# Power_Conditioning.net
KiCad netlist of a schematic drawn in Altium Designer
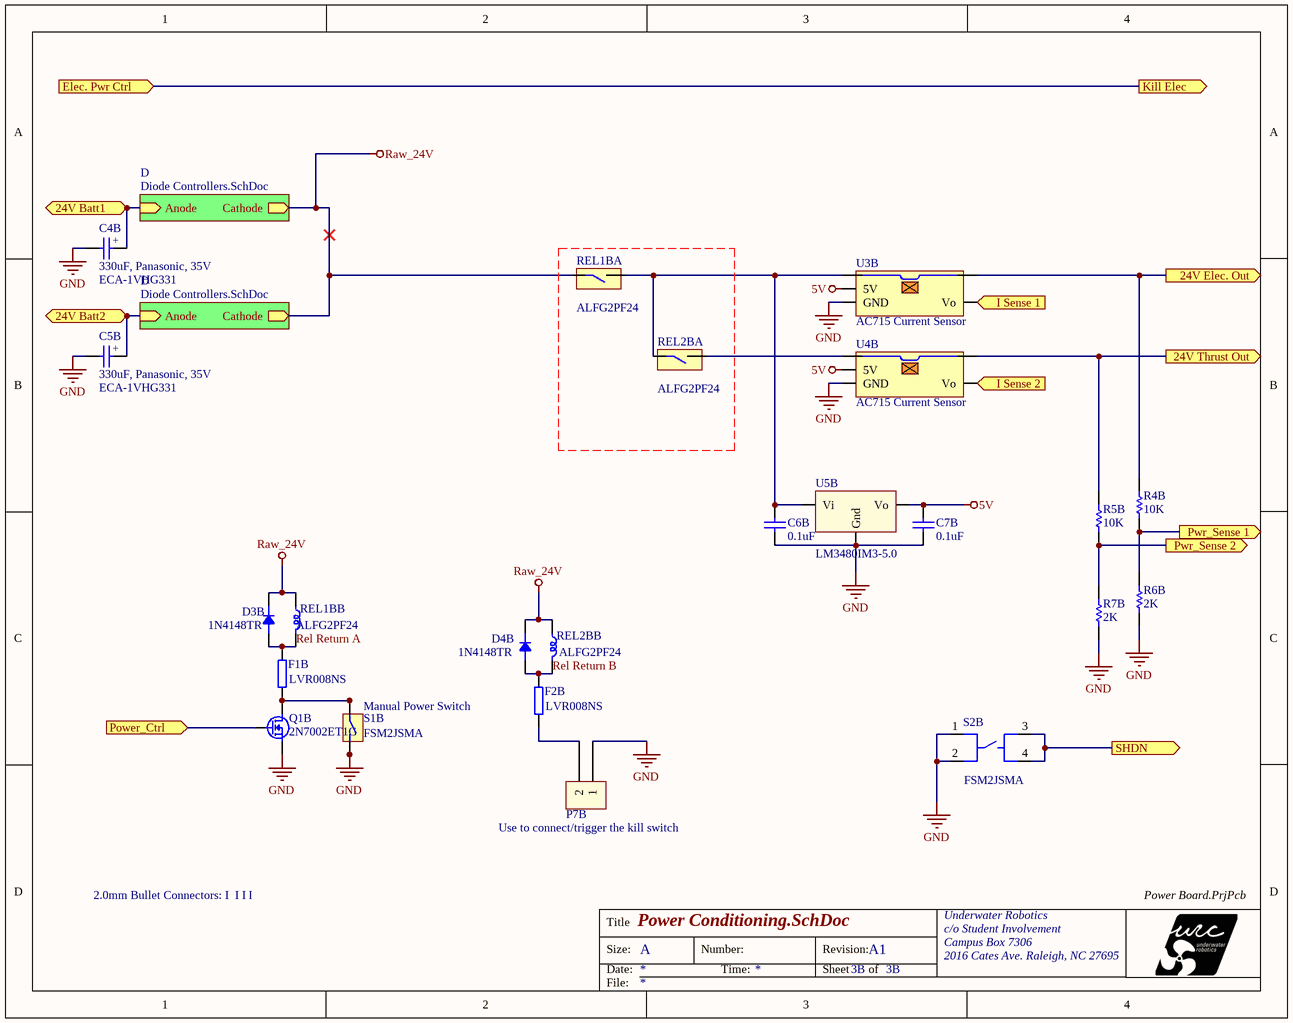
[diagram p0: Power Conditioning.SchDoc]

(export (version "E")
  (design (tool "Eeschema 10.0.6"))
  (components
    (comp (ref "C4B")
      (value "330uF, Panasonic, 35V")
      (footprint "10mm Radial Cap, Generic")
      (fields (field (name "MANUFACTURER PART NUMBER") "ECA-1VHG331"))
      (libsource (lib "Capacitors SchLib") (part "330uF, Panasonic, 35V"))
    )
    (comp (ref "C5B")
      (value "330uF, Panasonic, 35V")
      (footprint "10mm Radial Cap, Generic")
      (fields (field (name "MANUFACTURER PART NUMBER") "ECA-1VHG331"))
      (libsource (lib "Capacitors SchLib") (part "330uF, Panasonic, 35V"))
    )
    (comp (ref "C6B")
      (value "0.1uF")
      (footprint "C0805")
      (description "Ceramic MLCC, AVX, X5R Dielectric")
      (fields
        (field (name "MANUFACTURER PART NUMBER") "08055C104JAT2A")
        (field (name "Comment") "0.1uF, C0805, AVX")
      )
      (libsource (lib "Capacitors SchLib") (part "0.1uF, C0805, AVX"))
    )
    (comp (ref "C7B")
      (value "0.1uF")
      (footprint "C0805")
      (description "Ceramic MLCC, AVX, X5R Dielectric")
      (fields
        (field (name "MANUFACTURER PART NUMBER") "08055C104JAT2A")
        (field (name "Comment") "0.1uF, C0805, AVX")
      )
      (libsource (lib "Capacitors SchLib") (part "0.1uF, C0805, AVX"))
    )
    (comp (ref "D3B")
      (value "Diode")
      (footprint "DO-35-0.3")
      (description "General Purpose Diode")
      (fields (field (name "MANUFACTURER PART NUMBER") "1N4148TR"))
      (libsource (lib "URC") (part "Diode"))
    )
    (comp (ref "D4B")
      (value "Diode")
      (footprint "DO-35-0.3")
      (description "General Purpose Diode")
      (fields (field (name "MANUFACTURER PART NUMBER") "1N4148TR"))
      (libsource (lib "URC") (part "Diode"))
    )
    (comp (ref "F1B")
      (value "PTC Fuse, LVR008NS")
      (footprint "LVR008NS - Resettable Fuse")
      (description "Generic Fuse")
      (fields (field (name "MANUFACTURER PART NUMBER") "LVR008NS"))
      (libsource (lib "URC") (part "PTC Fuse, LVR008NS"))
    )
    (comp (ref "F2B")
      (value "PTC Fuse, LVR008NS")
      (footprint "LVR008NS - Resettable Fuse")
      (description "Generic Fuse")
      (fields (field (name "MANUFACTURER PART NUMBER") "LVR008NS"))
      (libsource (lib "URC") (part "PTC Fuse, LVR008NS"))
    )
    (comp (ref "i1B")
      (value "2.0mm Bullet Connector (Placeholder)")
      (description "Typical 2.0mm bullet connector used in RC Electronics")
      (libsource (lib "") (part "2.0mm Bullet Connector (Placeholder)_1"))
    )
    (comp (ref "i2B")
      (value "2.0mm Bullet Connector (Placeholder)")
      (description "Typical 2.0mm bullet connector used in RC Electronics")
      (libsource (lib "URC") (part "2.0mm Bullet Connector (Placeholder)"))
    )
    (comp (ref "i3B")
      (value "2.0mm Bullet Connector (Placeholder)")
      (description "Typical 2.0mm bullet connector used in RC Electronics")
      (libsource (lib "URC") (part "2.0mm Bullet Connector (Placeholder)"))
    )
    (comp (ref "i4B")
      (value "2.0mm Bullet Connector (Placeholder)")
      (description "Typical 2.0mm bullet connector used in RC Electronics")
      (libsource (lib "URC") (part "2.0mm Bullet Connector (Placeholder)"))
    )
    (comp (ref "P7B")
      (value "Header")
      (footprint "1x2 Header")
      (description "1x2 Header")
      (libsource (lib "URC_Lib") (part "1x2 Header"))
    )
    (comp (ref "Q1B")
      (value "N-MOSFET")
      (footprint "2N7002-SOT23")
      (description "N-Channel MOSFET")
      (fields (field (name "MANUFACTURER PART NUMBER") "2N7002ET1G"))
      (libsource (lib "URC") (part "N-MOSFET"))
    )
    (comp (ref "R4B")
      (value "10K")
      (footprint "R0603")
      (description "Resistor")
      (fields (field (name "TOLERANCE") "1%") (field (name "MANUFACTURER PART NUMBER") "RC0603FR-1010KL"))
      (libsource (lib "Resistors SchLib") (part "10k, 1%, 100mW, Yageo, R0603"))
    )
    (comp (ref "R5B")
      (value "10K")
      (footprint "R0603")
      (description "Resistor")
      (fields (field (name "TOLERANCE") "1%") (field (name "MANUFACTURER PART NUMBER") "RC0603FR-1010KL"))
      (libsource (lib "Resistors SchLib") (part "10k, 1%, 100mW, Yageo, R0603"))
    )
    (comp (ref "R6B")
      (value "2K")
      (footprint "R0603")
      (description "Resistor")
      (fields (field (name "TOLERANCE") "1%") (field (name "MANUFACTURER PART NUMBER") "RC0603FR-072KL"))
      (libsource (lib "Resistors SchLib") (part "2k, 1%, 100mW, Yageo, R0603"))
    )
    (comp (ref "R7B")
      (value "2K")
      (footprint "R0603")
      (description "Resistor")
      (fields (field (name "TOLERANCE") "1%") (field (name "MANUFACTURER PART NUMBER") "RC0603FR-072KL"))
      (libsource (lib "Resistors SchLib") (part "2k, 1%, 100mW, Yageo, R0603"))
    )
    (comp (ref "REL1B")
      (value "ALFG2PF24")
      (footprint "LF-G Series Relay")
      (description "24V, 33A General Purpose Relay")
      (fields (field (name "MANUFACTURER PART NUMBER") "ALFG2PF24"))
      (libsource (lib "Panasonic SchLib") (part "ALFG2PF24"))
    )
    (comp (ref "REL2B")
      (value "ALFG2PF24")
      (footprint "LF-G Series Relay")
      (description "24V, 33A General Purpose Relay")
      (fields (field (name "MANUFACTURER PART NUMBER") "ALFG2PF24"))
      (libsource (lib "Panasonic SchLib") (part "ALFG2PF24"))
    )
    (comp (ref "S1B")
      (value "FSM2JSMA")
      (footprint "FSM2JSMA")
      (description "Tactile Switch (OFF-MOM)")
      (fields (field (name "MANUFACTURER PART NUMBER") "FSM2JSMA"))
      (libsource (lib "URC") (part "FSM2JSMA"))
    )
    (comp (ref "S2B")
      (value "FSM2JSMA")
      (footprint "FSM2JSMA")
      (description "Tactile Switch (OFF-MOM)")
      (fields (field (name "MANUFACTURER PART NUMBER") "FSM2JSMA"))
      (libsource (lib "") (part "FSM2JSMA_1"))
    )
    (comp (ref "U3B")
      (value "AC715 Current Sensor")
      (footprint "AC715 Current Sensor")
      (fields (field (name "MANUFACTURER PART NUMBER") "1186"))
      (libsource (lib "URC") (part "AC715 Current Sensor"))
    )
    (comp (ref "U4B")
      (value "AC715 Current Sensor")
      (footprint "AC715 Current Sensor")
      (fields (field (name "MANUFACTURER PART NUMBER") "1186"))
      (libsource (lib "URC") (part "AC715 Current Sensor"))
    )
    (comp (ref "U5B")
      (value "LM3480")
      (footprint "LM4040-SOT23-3")
      (description "5V, 0.1A Fixed LDO")
      (fields (field (name "MANUFACTURER PART NUMBER") "LM3480IM3-5.0"))
      (libsource (lib "URC") (part "LM3480"))
    )
  )
  (nets
    (net (code "1") (name "/24V Batt1") (class "Default")
      (node (ref "C4B") (pin "1") (pinfunction "+_1") (pintype "passive"))
    )
    (net (code "2") (name "/24V Batt2") (class "Default")
      (node (ref "C5B") (pin "1") (pinfunction "+_1") (pintype "passive"))
    )
    (net (code "3") (name "/24V Elec. Out") (class "Default")
      (node (ref "R4B") (pin "2") (pinfunction "2_2") (pintype "passive"))
      (node (ref "U3B") (pin "2") (pinfunction "2_2") (pintype "passive"))
    )
    (net (code "4") (name "/24V Thrust Out") (class "Default")
      (node (ref "R5B") (pin "2") (pinfunction "2_2") (pintype "passive"))
      (node (ref "U4B") (pin "2") (pinfunction "2_2") (pintype "passive"))
    )
    (net (code "6") (name "/I Sense 1") (class "Default")
      (node (ref "U3B") (pin "4") (pinfunction "Vo_4") (pintype "passive"))
    )
    (net (code "7") (name "/I Sense 2") (class "Default")
      (node (ref "U4B") (pin "4") (pinfunction "Vo_4") (pintype "passive"))
    )
    (net (code "8") (name "/Power_Ctrl") (class "Default")
      (node (ref "Q1B") (pin "G") (pinfunction "GATE_G") (pintype "passive"))
    )
    (net (code "9") (name "/Pwr_Sense 1") (class "Default")
      (node (ref "R4B") (pin "1") (pinfunction "1_1") (pintype "passive"))
      (node (ref "R6B") (pin "2") (pinfunction "2_2") (pintype "passive"))
    )
    (net (code "10") (name "/Pwr_Sense 2") (class "Default")
      (node (ref "R5B") (pin "1") (pinfunction "1_1") (pintype "passive"))
      (node (ref "R7B") (pin "2") (pinfunction "2_2") (pintype "passive"))
    )
    (net (code "11") (name "/Rel Return A") (class "Default")
      (node (ref "D3B") (pin "1") (pinfunction "1_1") (pintype "passive"))
      (node (ref "F1B") (pin "1") (pinfunction "1_1") (pintype "passive"))
      (node (ref "REL1B") (pin "1") (pinfunction "1_1") (pintype "passive"))
    )
    (net (code "12") (name "/Rel Return B") (class "Default")
      (node (ref "D4B") (pin "1") (pinfunction "1_1") (pintype "passive"))
      (node (ref "F2B") (pin "1") (pinfunction "1_1") (pintype "passive"))
      (node (ref "REL2B") (pin "1") (pinfunction "1_1") (pintype "passive"))
    )
    (net (code "13") (name "/SHDN") (class "Default")
      (node (ref "S2B") (pin "3") (pinfunction "3_3") (pintype "passive"))
      (node (ref "S2B") (pin "4") (pinfunction "4_4") (pintype "passive"))
    )
    (net (code "14") (name "5V") (class "Default")
      (node (ref "C7B") (pin "1") (pinfunction "+_1") (pintype "passive"))
      (node (ref "U3B") (pin "5") (pinfunction "5V_5") (pintype "passive"))
      (node (ref "U4B") (pin "5") (pinfunction "5V_5") (pintype "passive"))
      (node (ref "U5B") (pin "2") (pinfunction "Vo_2") (pintype "power_in"))
    )
    (net (code "15") (name "GND") (class "Default")
      (node (ref "C4B") (pin "2") (pinfunction "2_2") (pintype "passive"))
      (node (ref "C5B") (pin "2") (pinfunction "2_2") (pintype "passive"))
      (node (ref "C6B") (pin "2") (pinfunction "2_2") (pintype "passive"))
      (node (ref "C7B") (pin "2") (pinfunction "2_2") (pintype "passive"))
      (node (ref "P7B") (pin "1") (pinfunction "1_1") (pintype "passive"))
      (node (ref "Q1B") (pin "S") (pinfunction "SOURCE_S") (pintype "passive"))
      (node (ref "R6B") (pin "1") (pinfunction "1_1") (pintype "passive"))
      (node (ref "R7B") (pin "1") (pinfunction "1_1") (pintype "passive"))
      (node (ref "S1B") (pin "3") (pinfunction "3_3") (pintype "passive"))
      (node (ref "S1B") (pin "4") (pinfunction "4_4") (pintype "passive"))
      (node (ref "S2B") (pin "1") (pinfunction "1_1") (pintype "passive"))
      (node (ref "S2B") (pin "2") (pinfunction "2_2") (pintype "passive"))
      (node (ref "U3B") (pin "3") (pinfunction "GND_3") (pintype "passive"))
      (node (ref "U4B") (pin "3") (pinfunction "GND_3") (pintype "passive"))
      (node (ref "U5B") (pin "1") (pinfunction "Gnd_1") (pintype "power_in"))
    )
    (net (code "16") (name "Net-(C6B-+)") (class "Default")
      (node (ref "C6B") (pin "1") (pinfunction "+_1") (pintype "passive"))
      (node (ref "REL1B") (pin "3") (pinfunction "3_3") (pintype "passive"))
      (node (ref "REL2B") (pin "4") (pinfunction "4_4") (pintype "passive"))
      (node (ref "U3B") (pin "1") (pinfunction "1_1") (pintype "passive"))
      (node (ref "U5B") (pin "3") (pinfunction "Vi_3") (pintype "passive"))
    )
    (net (code "17") (name "Net-(F2B-Pad2)") (class "Default")
      (node (ref "F2B") (pin "2") (pinfunction "2_2") (pintype "passive"))
      (node (ref "P7B") (pin "2") (pinfunction "2_2") (pintype "passive"))
    )
    (net (code "18") (name "Net-(Q1B-DRAIN)") (class "Default")
      (node (ref "F1B") (pin "2") (pinfunction "2_2") (pintype "passive"))
      (node (ref "Q1B") (pin "D") (pinfunction "DRAIN_D") (pintype "passive"))
      (node (ref "S1B") (pin "1") (pinfunction "1_1") (pintype "passive"))
      (node (ref "S1B") (pin "2") (pinfunction "2_2") (pintype "passive"))
    )
    (net (code "19") (name "Net-(REL2B-Pad3)") (class "Default")
      (node (ref "REL2B") (pin "3") (pinfunction "3_3") (pintype "passive"))
      (node (ref "U4B") (pin "1") (pinfunction "1_1") (pintype "passive"))
    )
    (net (code "20") (name "Raw_24V") (class "Default")
      (node (ref "D3B") (pin "2") (pinfunction "2_2") (pintype "passive"))
      (node (ref "D4B") (pin "2") (pinfunction "2_2") (pintype "passive"))
      (node (ref "REL1B") (pin "2") (pinfunction "2_2") (pintype "passive"))
      (node (ref "REL1B") (pin "4") (pinfunction "4_4") (pintype "passive"))
      (node (ref "REL2B") (pin "2") (pinfunction "2_2") (pintype "passive"))
    )
  )
)
